# IMU_BMI085.net
KiCad netlist of a schematic drawn in Altium Designer
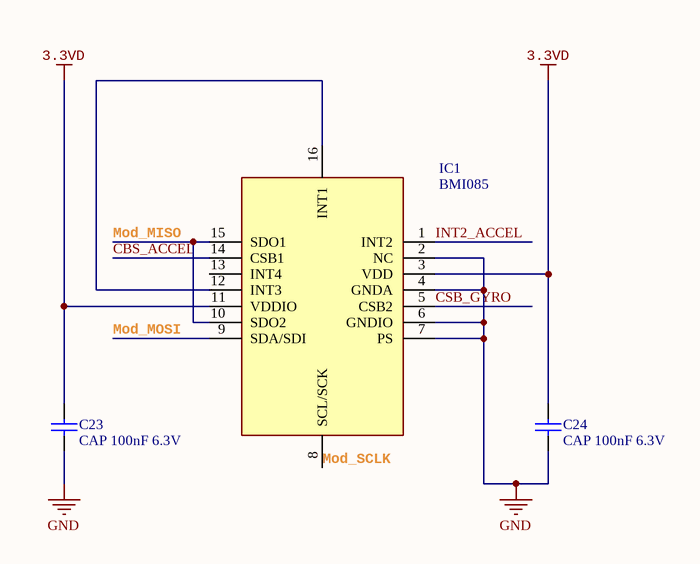
[diagram p0: IMU_BMI085.SchDoc]

(export (version "E")
  (design (tool "Eeschema 10.0.6"))
  (components
    (comp (ref "C23")
      (value "CAP 100nF 6.3V")
      (footprint "CAPC0603(1608)100_N")
      (description "CAP 100nF 6.3V ±10% 0603 (1608 Metric) Thickness 1mm SMD")
      (fields (field (name "TOLERANCE") "Â±10%"))
      (libsource (lib "Altium Content Vault") (part "CAP"))
    )
    (comp (ref "C24")
      (value "CAP 100nF 6.3V")
      (footprint "CAPC0603(1608)100_N")
      (description "CAP 100nF 6.3V ±10% 0603 (1608 Metric) Thickness 1mm SMD")
      (fields (field (name "TOLERANCE") "Â±10%"))
      (libsource (lib "Altium Content Vault") (part "CAP"))
    )
    (comp (ref "IC1")
      (value "BMI085")
      (footprint "SamacSys:BMI085")
      (description "Integrated Circuit")
      (fields (field (name "MOUSER PART NUMBER") "262-BMI085"))
      (libsource (lib "*") (part "BMI085"))
    )
  )
  (nets
    (net (code "1") (name "/CBS_ACCEL") (class "Default")
      (node (ref "IC1") (pin "14") (pinfunction "CSB1_14") (pintype "passive"))
    )
    (net (code "2") (name "/CSB_GYRO") (class "Default")
      (node (ref "IC1") (pin "5") (pinfunction "CSB2_5") (pintype "passive"))
    )
    (net (code "3") (name "/INT2_ACCEL") (class "Default")
      (node (ref "IC1") (pin "1") (pinfunction "INT2_1") (pintype "passive"))
    )
    (net (code "4") (name "/Mod_MISO") (class "Default")
      (node (ref "IC1") (pin "10") (pinfunction "SDO2_10") (pintype "passive"))
      (node (ref "IC1") (pin "15") (pinfunction "SDO1_15") (pintype "passive"))
    )
    (net (code "5") (name "/Mod_MOSI") (class "Default")
      (node (ref "IC1") (pin "9") (pinfunction "SDA/SDI_9") (pintype "passive"))
    )
    (net (code "6") (name "/Mod_SCLK") (class "Default")
      (node (ref "IC1") (pin "8") (pinfunction "SCL/SCK_8") (pintype "passive"))
    )
    (net (code "7") (name "3.3VD") (class "Default")
      (node (ref "C23") (pin "2") (pinfunction "2_2") (pintype "passive"))
      (node (ref "C24") (pin "2") (pinfunction "2_2") (pintype "passive"))
      (node (ref "IC1") (pin "11") (pinfunction "VDDIO_11") (pintype "passive"))
      (node (ref "IC1") (pin "3") (pinfunction "VDD_3") (pintype "passive"))
    )
    (net (code "8") (name "GND") (class "Default")
      (node (ref "C23") (pin "1") (pinfunction "1_1") (pintype "passive"))
      (node (ref "C24") (pin "1") (pinfunction "1_1") (pintype "passive"))
      (node (ref "IC1") (pin "2") (pinfunction "NC_2") (pintype "passive"))
      (node (ref "IC1") (pin "4") (pinfunction "GNDA_4") (pintype "passive"))
      (node (ref "IC1") (pin "6") (pinfunction "GNDIO_6") (pintype "passive"))
      (node (ref "IC1") (pin "7") (pinfunction "PS_7") (pintype "passive"))
    )
    (net (code "9") (name "Net-(IC1-INT1)") (class "Default")
      (node (ref "IC1") (pin "12") (pinfunction "INT3_12") (pintype "passive"))
      (node (ref "IC1") (pin "16") (pinfunction "INT1_16") (pintype "passive"))
    )
    (net (code "10") (name "unconnected-(IC1-INT4-Pad13)") (class "Default")
      (node (ref "IC1") (pin "13") (pinfunction "INT4_13") (pintype "passive"))
    )
  )
)
